# SIM800C_BoardSCH.net
KiCad netlist of a schematic drawn in Altium Designer
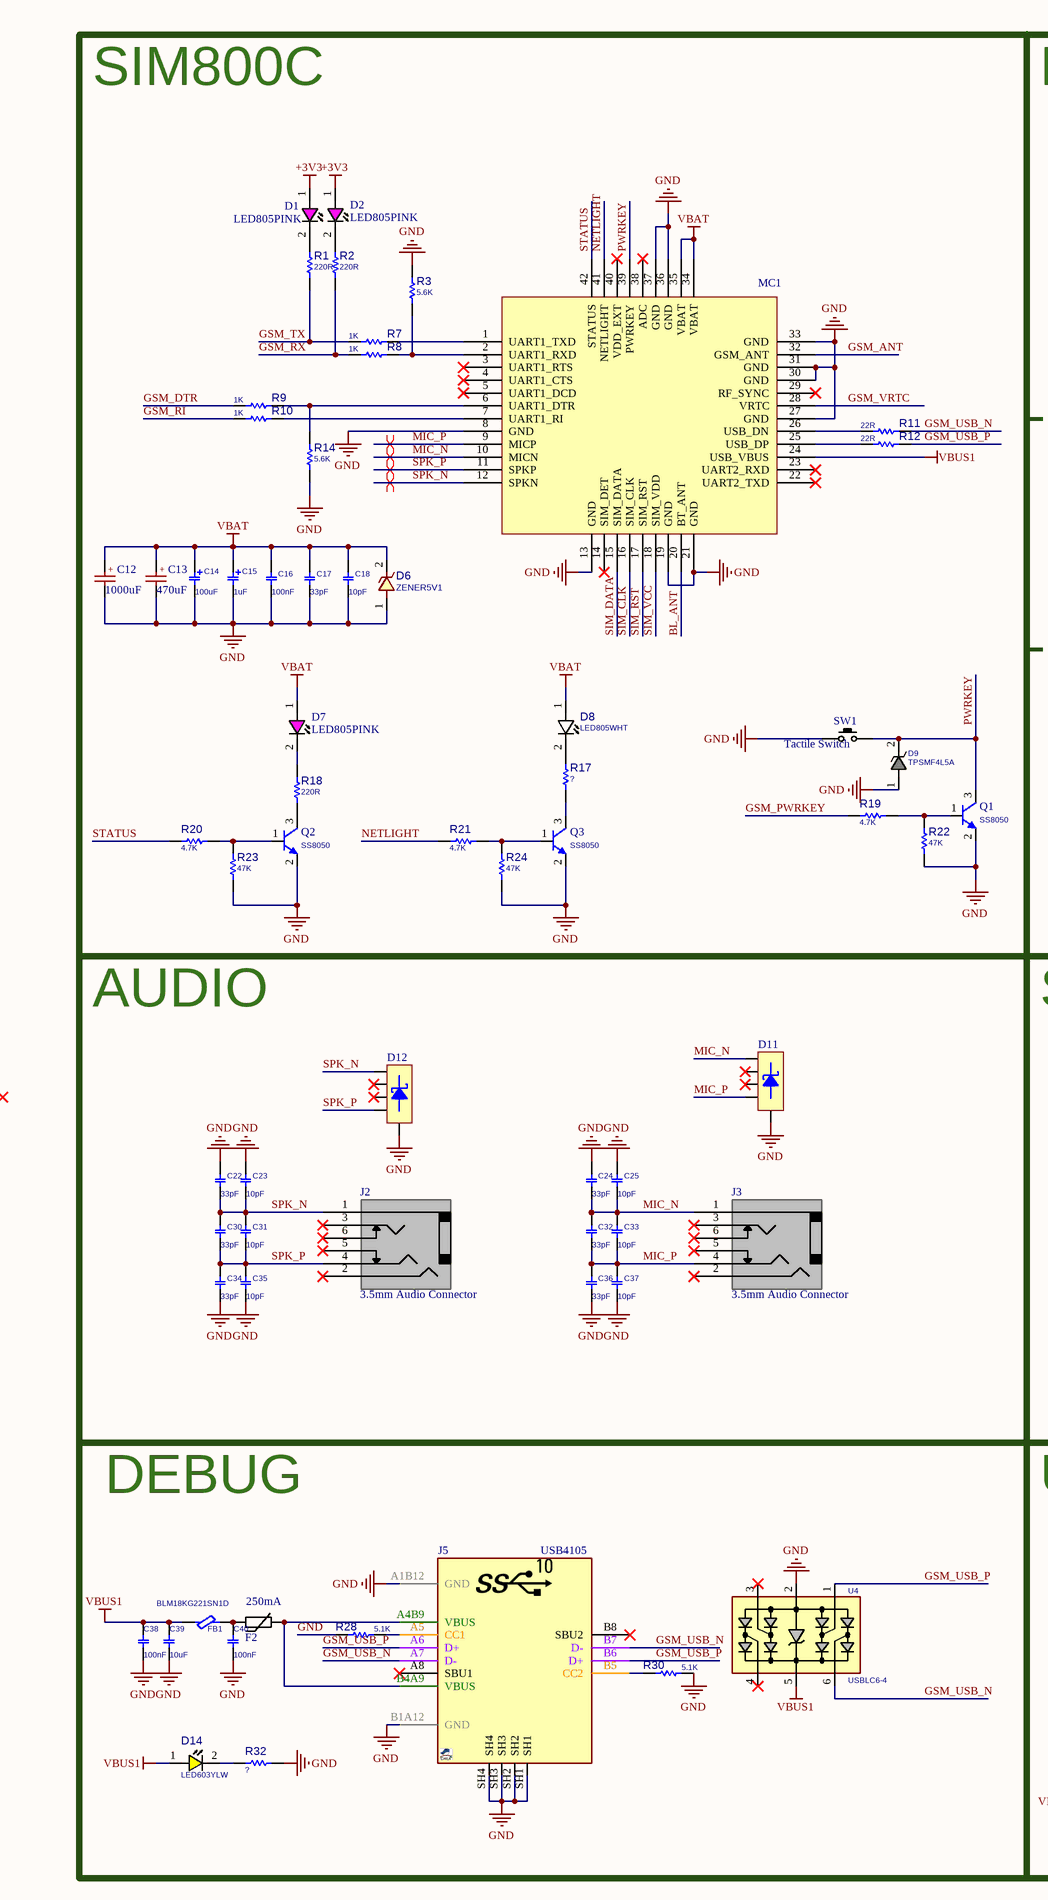
[diagram p0: SIM800C_BoardSCH.SchDoc, left]
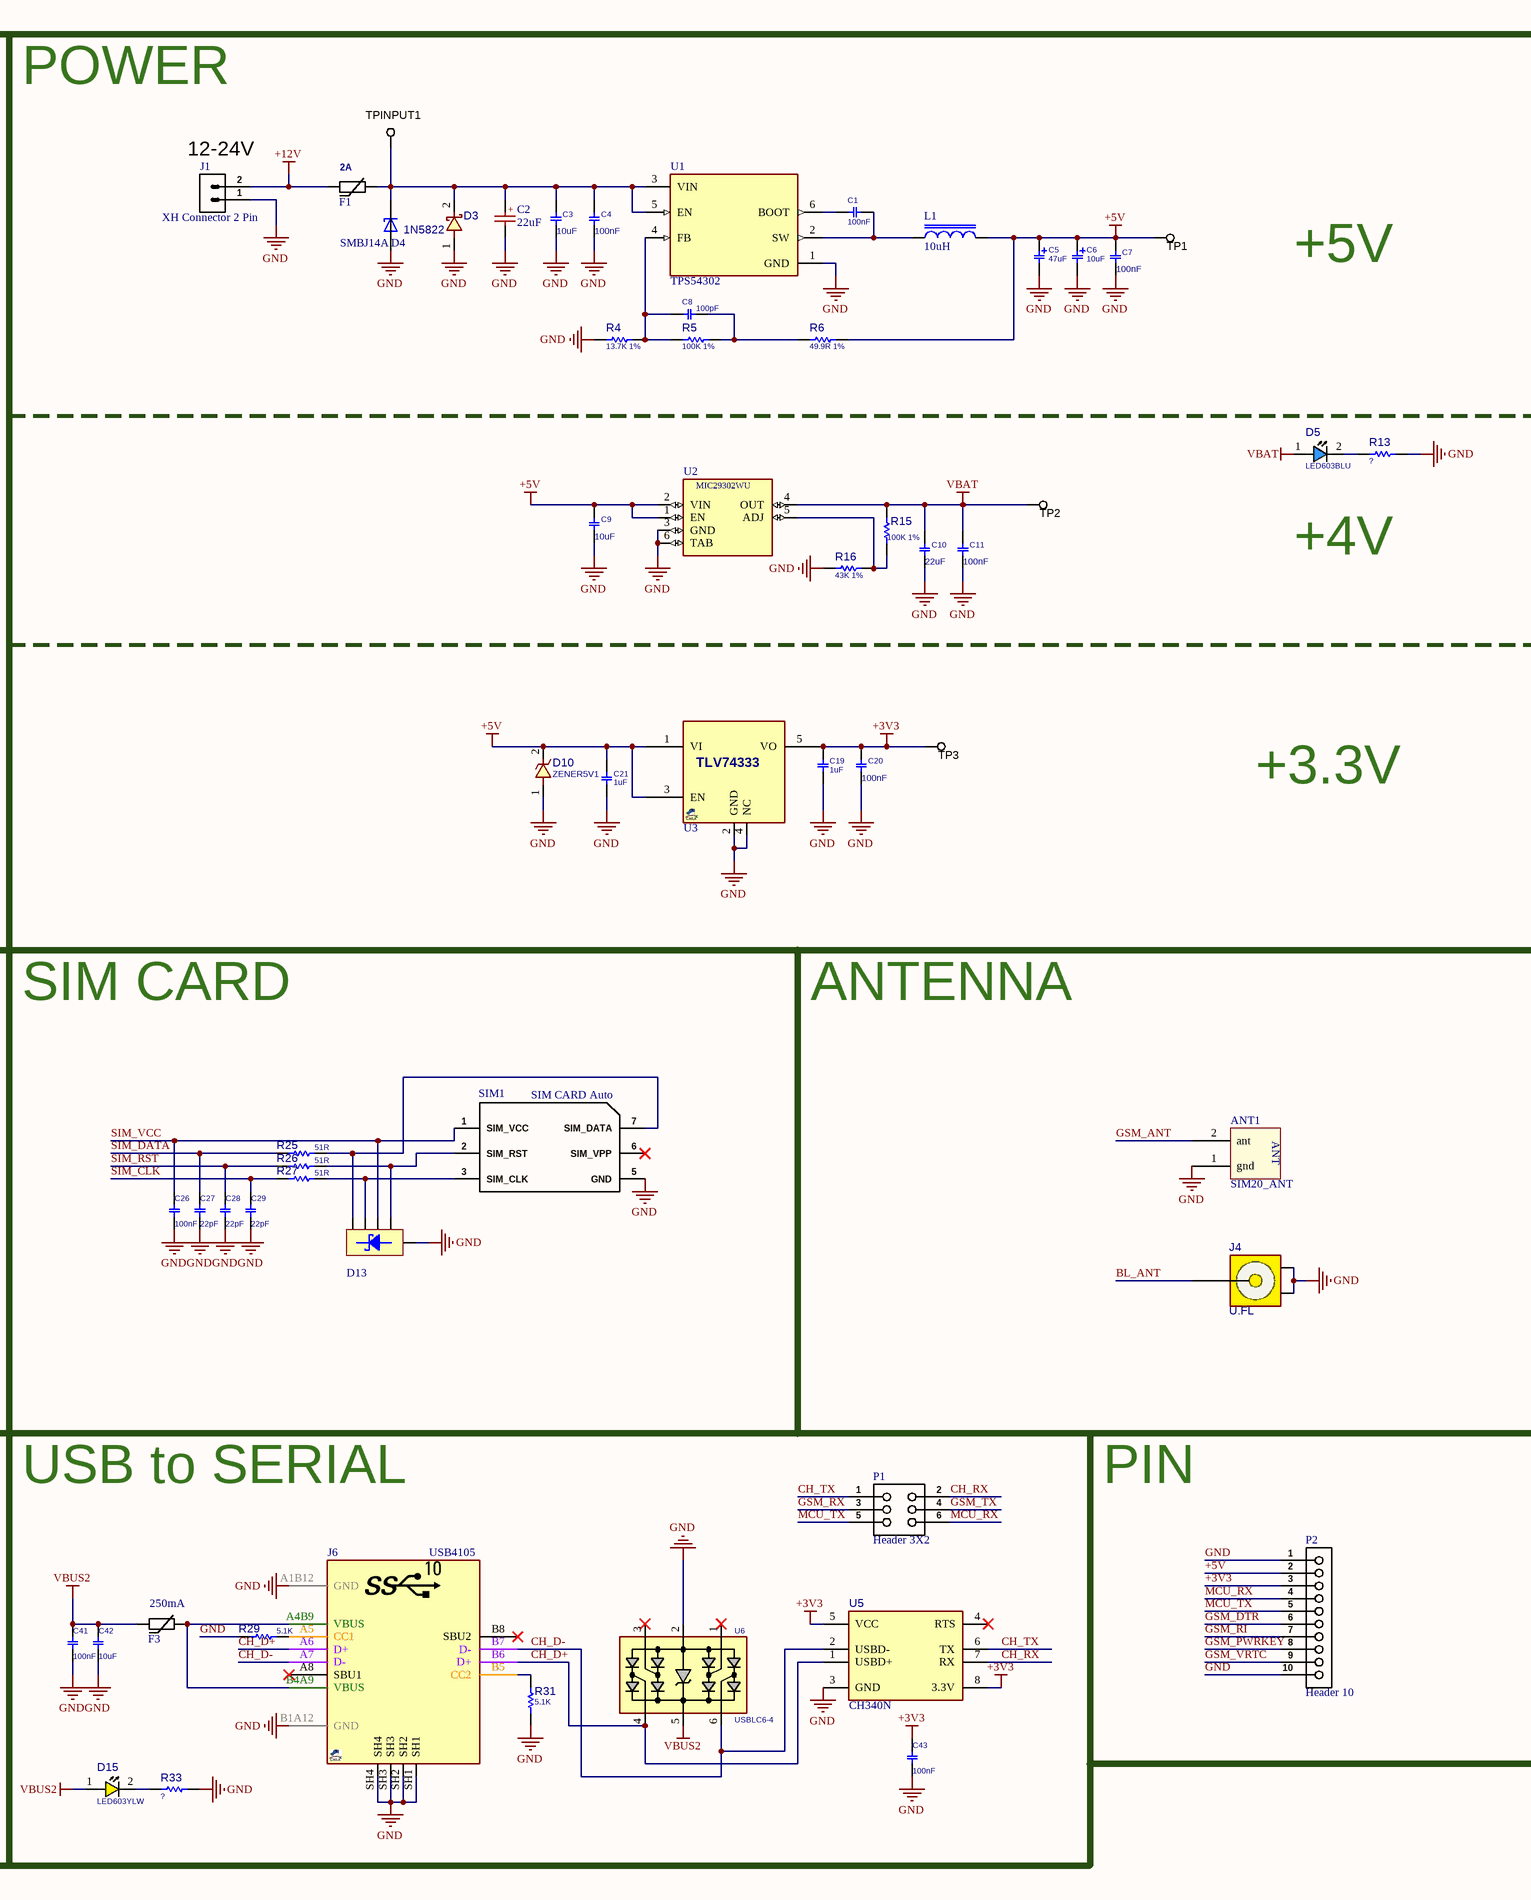
[diagram p1: SIM800C_BoardSCH.SchDoc, right]

(export (version "E")
  (design (tool "Eeschema 10.0.6"))
  (components
    (comp (ref "ANT1")
      (value "SIM20_ANT")
      (footprint "MY_SIM20_ANT")
      (description "ANT")
      (libsource (lib "AMINLIB") (part "SIM20_ANT"))
    )
    (comp (ref "C1")
      (value "100nF")
      (footprint "C0603")
      (description "CAP, MLCC, -F, -V, MATERIAL, -%, 0201")
      (fields (field (name "MANF_P#") "MANF_PART#"))
      (libsource (lib "passive_smd") (part "CAP_SMD_MLCC_0603"))
    )
    (comp (ref "C2")
      (value "22uF")
      (footprint "Cap SMD 6.3x5.4mm")
      (description "SMD Aluminum Electrolytic Capacitor")
      (fields
        (field (name "VOLTAGE") "12v")
        (field (name "TOLERANCE") "5%")
        (field (name "PUBLISHER") "Majid Derhambakhsh")
      )
      (libsource (lib "mBedLab Altium Library (2024-04-20)") (part "CAP Electrolytic SMD"))
    )
    (comp (ref "C3")
      (value "10uF")
      (footprint "C1206")
      (description "CAP, MLCC")
      (fields (field (name "MANF_P#") "MANF_PART#"))
      (libsource (lib "passive_smd") (part "CAP_SMD_MLCC_1206"))
    )
    (comp (ref "C4")
      (value "100nF")
      (footprint "C1206")
      (description "CAP, MLCC")
      (fields (field (name "MANF_P#") "MANF_PART#"))
      (libsource (lib "passive_smd") (part "CAP_SMD_MLCC_1206"))
    )
    (comp (ref "C5")
      (value "47uF")
      (footprint "C_TN_3216")
      (description "CAP, SMD, TAN,")
      (libsource (lib "passive_smd") (part "CAP_SMD_TAN"))
    )
    (comp (ref "C6")
      (value "10uF")
      (footprint "C_TN_3216")
      (description "CAP, SMD, TAN,")
      (libsource (lib "passive_smd") (part "CAP_SMD_TAN"))
    )
    (comp (ref "C7")
      (value "100nF")
      (footprint "C1206")
      (description "CAP, MLCC")
      (fields (field (name "MANF_P#") "MANF_PART#"))
      (libsource (lib "passive_smd") (part "CAP_SMD_MLCC_1206"))
    )
    (comp (ref "C8")
      (value "100pF")
      (footprint "C0603")
      (description "CAP, MLCC, -F, -V, MATERIAL, -%, 0201")
      (fields (field (name "MANF_P#") "MANF_PART#"))
      (libsource (lib "passive_smd") (part "CAP_SMD_MLCC_0603"))
    )
    (comp (ref "C9")
      (value "10uF")
      (footprint "C1206")
      (description "CAP, MLCC")
      (fields (field (name "MANF_P#") "MANF_PART#"))
      (libsource (lib "passive_smd") (part "CAP_SMD_MLCC_1206"))
    )
    (comp (ref "C10")
      (value "22uF")
      (footprint "C1206")
      (description "CAP, MLCC")
      (fields (field (name "MANF_P#") "MANF_PART#"))
      (libsource (lib "passive_smd") (part "CAP_SMD_MLCC_1206"))
    )
    (comp (ref "C11")
      (value "100nF")
      (footprint "C1206")
      (description "CAP, MLCC")
      (fields (field (name "MANF_P#") "MANF_PART#"))
      (libsource (lib "passive_smd") (part "CAP_SMD_MLCC_1206"))
    )
    (comp (ref "C12")
      (value "1000uF")
      (footprint "Cap SMD 8x10mm")
      (description "SMD Aluminum Electrolytic Capacitor")
      (fields
        (field (name "VOLTAGE") "12v")
        (field (name "TOLERANCE") "5%")
        (field (name "PUBLISHER") "Majid Derhambakhsh")
      )
      (libsource (lib "mBedLab Altium Library (2024-04-20)") (part "CAP Electrolytic SMD"))
    )
    (comp (ref "C13")
      (value "470uF")
      (footprint "Cap SMD 6.3x7.7mm")
      (description "SMD Aluminum Electrolytic Capacitor")
      (fields
        (field (name "VOLTAGE") "12v")
        (field (name "TOLERANCE") "5%")
        (field (name "PUBLISHER") "Majid Derhambakhsh")
      )
      (libsource (lib "mBedLab Altium Library (2024-04-20)") (part "CAP Electrolytic SMD"))
    )
    (comp (ref "C14")
      (value "100uF")
      (footprint "C_TN_3528_BLK")
      (description "CAP, SMD, TAN")
      (fields (field (name "MANF") "VISHAY") (field (name "MANF_P#") "T55A106M6R3C0300"))
      (libsource (lib "AVR_RCS") (part "CAP_SMD_TAN_4"))
    )
    (comp (ref "C15")
      (value "1uF")
      (footprint "C_TN_3216")
      (description "CAP, SMD, TAN,")
      (libsource (lib "passive_smd") (part "CAP_SMD_TAN"))
    )
    (comp (ref "C16")
      (value "100nF")
      (footprint "C0603")
      (description "CAP, MLCC, -F, -V, MATERIAL, -%, 0201")
      (fields (field (name "MANF_P#") "MANF_PART#"))
      (libsource (lib "passive_smd") (part "CAP_SMD_MLCC_0603"))
    )
    (comp (ref "C17")
      (value "33pF")
      (footprint "C0603")
      (description "CAP, MLCC, -F, -V, MATERIAL, -%, 0201")
      (fields (field (name "MANF_P#") "MANF_PART#"))
      (libsource (lib "passive_smd") (part "CAP_SMD_MLCC_0603"))
    )
    (comp (ref "C18")
      (value "10pF")
      (footprint "C0603")
      (description "CAP, MLCC, -F, -V, MATERIAL, -%, 0201")
      (fields (field (name "MANF_P#") "MANF_PART#"))
      (libsource (lib "passive_smd") (part "CAP_SMD_MLCC_0603"))
    )
    (comp (ref "C19")
      (value "1uF")
      (footprint "C1206")
      (description "CAP, MLCC, -F, -V, MATERIAL, -%, 0201")
      (fields (field (name "MANF_P#") "MANF_PART#"))
      (libsource (lib "passive_smd") (part "CAP_SMD_MLCC_1206"))
    )
    (comp (ref "C20")
      (value "100nF")
      (footprint "C1206")
      (description "CAP, MLCC")
      (fields (field (name "MANF_P#") "MANF_PART#"))
      (libsource (lib "passive_smd") (part "CAP_SMD_MLCC_1206"))
    )
    (comp (ref "C21")
      (value "1uF")
      (footprint "C1206")
      (description "CAP, MLCC, -F, -V, MATERIAL, -%, 0201")
      (fields (field (name "MANF_P#") "MANF_PART#"))
      (libsource (lib "passive_smd") (part "CAP_SMD_MLCC_1206"))
    )
    (comp (ref "C22")
      (value "33pF")
      (footprint "C0603")
      (description "CAP, MLCC, -F, -V, MATERIAL, -%, 0201")
      (fields (field (name "MANF_P#") "MANF_PART#"))
      (libsource (lib "passive_smd") (part "CAP_SMD_MLCC_0603"))
    )
    (comp (ref "C23")
      (value "10pF")
      (footprint "C0603")
      (description "CAP, MLCC, -F, -V, MATERIAL, -%, 0201")
      (fields (field (name "MANF_P#") "MANF_PART#"))
      (libsource (lib "passive_smd") (part "CAP_SMD_MLCC_0603"))
    )
    (comp (ref "C24")
      (value "33pF")
      (footprint "C0603")
      (description "CAP, MLCC, -F, -V, MATERIAL, -%, 0201")
      (fields (field (name "MANF_P#") "MANF_PART#"))
      (libsource (lib "passive_smd") (part "CAP_SMD_MLCC_0603"))
    )
    (comp (ref "C25")
      (value "10pF")
      (footprint "C0603")
      (description "CAP, MLCC, -F, -V, MATERIAL, -%, 0201")
      (fields (field (name "MANF_P#") "MANF_PART#"))
      (libsource (lib "passive_smd") (part "CAP_SMD_MLCC_0603"))
    )
    (comp (ref "C26")
      (value "100nF")
      (footprint "C0603")
      (description "CAP, MLCC, -F, -V, MATERIAL, -%, 0201")
      (fields (field (name "MANF_P#") "MANF_PART#"))
      (libsource (lib "passive_smd") (part "CAP_SMD_MLCC_0603"))
    )
    (comp (ref "C27")
      (value "22pF")
      (footprint "C0603")
      (description "CAP, MLCC, -F, -V, MATERIAL, -%, 0201")
      (fields (field (name "MANF_P#") "MANF_PART#"))
      (libsource (lib "passive_smd") (part "CAP_SMD_MLCC_0603"))
    )
    (comp (ref "C28")
      (value "22pF")
      (footprint "C0603")
      (description "CAP, MLCC, -F, -V, MATERIAL, -%, 0201")
      (fields (field (name "MANF_P#") "MANF_PART#"))
      (libsource (lib "passive_smd") (part "CAP_SMD_MLCC_0603"))
    )
    (comp (ref "C29")
      (value "22pF")
      (footprint "C0603")
      (description "CAP, MLCC, -F, -V, MATERIAL, -%, 0201")
      (fields (field (name "MANF_P#") "MANF_PART#"))
      (libsource (lib "passive_smd") (part "CAP_SMD_MLCC_0603"))
    )
    (comp (ref "C30")
      (value "33pF")
      (footprint "C0603")
      (description "CAP, MLCC, -F, -V, MATERIAL, -%, 0201")
      (fields (field (name "MANF_P#") "MANF_PART#"))
      (libsource (lib "passive_smd") (part "CAP_SMD_MLCC_0603"))
    )
    (comp (ref "C31")
      (value "10pF")
      (footprint "C0603")
      (description "CAP, MLCC, -F, -V, MATERIAL, -%, 0201")
      (fields (field (name "MANF_P#") "MANF_PART#"))
      (libsource (lib "passive_smd") (part "CAP_SMD_MLCC_0603"))
    )
    (comp (ref "C32")
      (value "33pF")
      (footprint "C0603")
      (description "CAP, MLCC, -F, -V, MATERIAL, -%, 0201")
      (fields (field (name "MANF_P#") "MANF_PART#"))
      (libsource (lib "passive_smd") (part "CAP_SMD_MLCC_0603"))
    )
    (comp (ref "C33")
      (value "10pF")
      (footprint "C0603")
      (description "CAP, MLCC, -F, -V, MATERIAL, -%, 0201")
      (fields (field (name "MANF_P#") "MANF_PART#"))
      (libsource (lib "passive_smd") (part "CAP_SMD_MLCC_0603"))
    )
    (comp (ref "C34")
      (value "33pF")
      (footprint "C0603")
      (description "CAP, MLCC, -F, -V, MATERIAL, -%, 0201")
      (fields (field (name "MANF_P#") "MANF_PART#"))
      (libsource (lib "passive_smd") (part "CAP_SMD_MLCC_0603"))
    )
    (comp (ref "C35")
      (value "10pF")
      (footprint "C0603")
      (description "CAP, MLCC, -F, -V, MATERIAL, -%, 0201")
      (fields (field (name "MANF_P#") "MANF_PART#"))
      (libsource (lib "passive_smd") (part "CAP_SMD_MLCC_0603"))
    )
    (comp (ref "C36")
      (value "33pF")
      (footprint "C0603")
      (description "CAP, MLCC, -F, -V, MATERIAL, -%, 0201")
      (fields (field (name "MANF_P#") "MANF_PART#"))
      (libsource (lib "passive_smd") (part "CAP_SMD_MLCC_0603"))
    )
    (comp (ref "C37")
      (value "10pF")
      (footprint "C0603")
      (description "CAP, MLCC, -F, -V, MATERIAL, -%, 0201")
      (fields (field (name "MANF_P#") "MANF_PART#"))
      (libsource (lib "passive_smd") (part "CAP_SMD_MLCC_0603"))
    )
    (comp (ref "C38")
      (value "100nF")
      (footprint "C0603")
      (description "CAP, MLCC, -F, -V, MATERIAL, -%, 0201")
      (fields (field (name "MANF_P#") "MANF_PART#"))
      (libsource (lib "passive_smd") (part "CAP_SMD_MLCC_0603"))
    )
    (comp (ref "C39")
      (value "10uF")
      (footprint "C0603")
      (description "CAP, MLCC, -F, -V, MATERIAL, -%, 0201")
      (fields (field (name "MANF_P#") "MANF_PART#"))
      (libsource (lib "passive_smd") (part "CAP_SMD_MLCC_0603"))
    )
    (comp (ref "C40")
      (value "100nF")
      (footprint "C0603")
      (description "CAP, MLCC, -F, -V, MATERIAL, -%, 0201")
      (fields (field (name "MANF_P#") "MANF_PART#"))
      (libsource (lib "passive_smd") (part "CAP_SMD_MLCC_0603"))
    )
    (comp (ref "C41")
      (value "100nF")
      (footprint "C0603")
      (description "CAP, MLCC, -F, -V, MATERIAL, -%, 0201")
      (fields (field (name "MANF_P#") "MANF_PART#"))
      (libsource (lib "passive_smd") (part "CAP_SMD_MLCC_0603"))
    )
    (comp (ref "C42")
      (value "10uF")
      (footprint "C0603")
      (description "CAP, MLCC, -F, -V, MATERIAL, -%, 0201")
      (fields (field (name "MANF_P#") "MANF_PART#"))
      (libsource (lib "passive_smd") (part "CAP_SMD_MLCC_0603"))
    )
    (comp (ref "C43")
      (value "100nF")
      (footprint "C0603")
      (description "CAP, MLCC, -F, -V, MATERIAL, -%, 0201")
      (fields (field (name "MANF_P#") "MANF_PART#"))
      (libsource (lib "passive_smd") (part "CAP_SMD_MLCC_0603"))
    )
    (comp (ref "D1")
      (value "LED805PINK")
      (footprint "LED_Pink_0805")
      (description "LED, SMD, 0805, PINK")
      (libsource (lib "Mehrdad") (part "LED_Pink"))
    )
    (comp (ref "D2")
      (value "LED805PINK")
      (footprint "LED_Pink_0805")
      (description "LED, SMD, 0805, PINK")
      (libsource (lib "Mehrdad") (part "LED_Pink"))
    )
    (comp (ref "D3")
      (value "1N5822")
      (footprint "D_SMA")
      (description "DIODE, SCHOTTKY, 40V, 3A")
      (fields (field (name "MANF") "DIODES"))
      (libsource (lib "diode") (part "DIODE_SMD_SCHOTTKY_1N5822"))
    )
    (comp (ref "D4")
      (value "SMBJ14A")
      (footprint "SMBJ14A")
      (description "TVS Diode Uni-directional 14V SMB")
      (libsource (lib "Mehrdad") (part "SMBJ14A"))
    )
    (comp (ref "D5")
      (value "LED603BLU")
      (footprint "LED0603BLU")
      (description "LED, SMD, 0603, BLUE")
      (fields (field (name "MANF") "MANF") (field (name "MANF_P#") "MANF_PART#"))
      (libsource (lib "led(diode)") (part "LED_SMD_0603_BLU"))
    )
    (comp (ref "D6")
      (value "ZENER5V1")
      (footprint "D_SOD123W")
      (description "DIODE, ZENER, 1W, 5.1V")
      (fields (field (name "MANF") "Diodes") (field (name "MANF_P#") "BZT52HC5V1WF-7"))
      (libsource (lib "AVR_RCS") (part "DIODE_SMD_ZENER_BZT52HC5V1"))
    )
    (comp (ref "D7")
      (value "LED805PINK")
      (footprint "LED_Pink_0805")
      (description "LED, SMD, 0805, PINK")
      (libsource (lib "Mehrdad") (part "LED_Pink"))
    )
    (comp (ref "D8")
      (value "LED805WHT")
      (footprint "LED0805WHT")
      (description "LED, SMD, 0805, WHITE")
      (fields (field (name "MANF") "MANF") (field (name "MANF_P#") "MANF_PART#"))
      (libsource (lib "led(diode)") (part "LED_SMD_0805_WHT"))
    )
    (comp (ref "D9")
      (value "TPSMF4L5A")
      (footprint "D_SOD123W")
      (description "TVS, ESD PROTECT")
      (fields (field (name "MANF_P#") "TPSMF4L33A") (field (name "MANF") "Littelfuse"))
      (libsource (lib "protect_tvs_esd_fuse") (part "TVS_TPSMF4L33A"))
    )
    (comp (ref "D10")
      (value "ZENER5V1")
      (footprint "D_SOD123W")
      (description "DIODE, ZENER, 1W, 5.1V")
      (fields (field (name "MANF") "Diodes") (field (name "MANF_P#") "BZT52HC5V1WF-7"))
      (libsource (lib "AVR_RCS") (part "DIODE_SMD_ZENER_BZT52HC5V1"))
    )
    (comp (ref "D11")
      (value "SMF-05")
      (footprint "SC70-5_N")
      (description "TVS Diode Array")
      (fields (field (name "VALIDATION") "Valid"))
      (libsource (lib "aKaReZa") (part "Semi_Diod_TVS_SMF05"))
    )
    (comp (ref "D12")
      (value "SMF-05")
      (footprint "SC70-5_N")
      (description "TVS Diode Array")
      (fields (field (name "VALIDATION") "Valid"))
      (libsource (lib "aKaReZa") (part "Semi_Diod_TVS_SMF05"))
    )
    (comp (ref "D13")
      (value "SMF-05")
      (footprint "SC70-5_N")
      (description "TVS Diode Array")
      (fields (field (name "VALIDATION") "Valid"))
      (libsource (lib "") (part "Semi_Diod_TVS_SMF05_1"))
    )
    (comp (ref "D14")
      (value "LED603YLW")
      (footprint "LED0603YLW")
      (description "LED, SMD, 0603, YELLOW")
      (fields (field (name "MANF") "MANF") (field (name "MANF_P#") "MANF_PART#"))
      (libsource (lib "led(diode)") (part "LED_SMD_0603_YLW"))
    )
    (comp (ref "D15")
      (value "LED603YLW")
      (footprint "LED0603YLW")
      (description "LED, SMD, 0603, YELLOW")
      (fields (field (name "MANF") "MANF") (field (name "MANF_P#") "MANF_PART#"))
      (libsource (lib "led(diode)") (part "LED_SMD_0603_YLW"))
    )
    (comp (ref "F1")
      (value "2A")
      (footprint "FUSE1206 (3216)")
      (fields (field (name "PUBLISHER") "Majid Derhambakhsh"))
      (libsource (lib "mBedLab Altium Library (2024-04-20)") (part "PPTC Resettable Fuses"))
    )
    (comp (ref "F2")
      (value "250mA")
      (footprint "FUSE0603 (1608)")
      (fields (field (name "PUBLISHER") "Majid Derhambakhsh"))
      (libsource (lib "mBedLab Altium Library (2024-04-20)") (part "PPTC Resettable Fuses"))
    )
    (comp (ref "F3")
      (value "250mA")
      (footprint "FUSE0603 (1608)")
      (fields (field (name "PUBLISHER") "Majid Derhambakhsh"))
      (libsource (lib "mBedLab Altium Library (2024-04-20)") (part "PPTC Resettable Fuses"))
    )
    (comp (ref "FB1")
      (value "BLM18KG221SN1D")
      (footprint "L0603")
      (description "FERRITE_Bead, 0603, 2A, 50mOhm, 120@100MHz")
      (fields (field (name "MANF") "MURATA") (field (name "MANF_P#") "BLM18PG121SN1D"))
      (libsource (lib "emi_filter") (part "FBEAD_SMD_BLM18PG121"))
    )
    (comp (ref "J1")
      (value "XH Connector 2 Pin")
      (footprint "XH 2 Pin Right (CWF) - 2.5mm")
      (description "XH, 2-Pin")
      (fields (field (name "PUBLISHER") "Majid Derhambakhsh"))
      (libsource (lib "mBedLab Altium Library (2024-04-20)") (part "XH 2"))
    )
    (comp (ref "J2")
      (value "3.5mm Audio Connector")
      (footprint "PJ311D")
      (libsource (lib "Mehrdad") (part "PJ311D"))
    )
    (comp (ref "J3")
      (value "3.5mm Audio Connector")
      (footprint "PJ311D")
      (libsource (lib "Mehrdad") (part "PJ311D"))
    )
    (comp (ref "J4")
      (value "U.FL")
      (footprint "UFL")
      (description "CONN, RF, U.FL, STRAIGHT, Ultra Miniature Coaxial")
      (fields
        (field (name "MANF_P#") "CONUFL001-SMD, U.FL-R-SMT-1(10), 128-0711-201")
        (field (name "MANF") "Linx, Hirose, Cinch")
      )
      (libsource (lib "conn_rf") (part "CONN_RF_UFL"))
    )
    (comp (ref "J5")
      (value "USB4105")
      (footprint "USBC_SMD_16_USB4105")
      (description "CONN, USB, Type C, USB 2.0, Right-Angle, SMD")
      (fields (field (name "MANF") "GCT") (field (name "MANF_P#") "USB4105-GF-A"))
      (libsource (lib "conn_usbc") (part "CONN_USBC_SMD_16_USB4105"))
    )
    (comp (ref "J6")
      (value "USB4105")
      (footprint "USBC_SMD_16_USB4105")
      (description "CONN, USB, Type C, USB 2.0, Right-Angle, SMD")
      (fields (field (name "MANF") "GCT") (field (name "MANF_P#") "USB4105-GF-A"))
      (libsource (lib "conn_usbc") (part "CONN_USBC_SMD_16_USB4105"))
    )
    (comp (ref "L1")
      (value "10uH")
      (footprint "SMD Inductor 1")
      (description "1210 (3225)  Part number : DFE322512F-100M=P2")
      (libsource (lib "Mehrdad") (part "SMD Inductor 1"))
    )
    (comp (ref "MC1")
      (value "Sim800C")
      (footprint "SIM800C")
      (description "SimCom GSM/GPRS Module")
      (fields (field (name "VALIDATION") "NT"))
      (libsource (lib "aKaReZa") (part "ModSen_Com_Sim800C"))
    )
    (comp (ref "P1")
      (value "Header 3X2")
      (footprint "HDR 2X3 Male Top")
      (description "Header, 3-Pin, Dual row")
      (fields (field (name "PUBLISHER") "Majid Derhambakhsh"))
      (libsource (lib "mBedLab Altium Library (2024-04-20)") (part "Header 3X2"))
    )
    (comp (ref "P2")
      (value "Header 10")
      (footprint "HDR 1X10 Male Top")
      (description "Header, 10-Pin")
      (fields (field (name "PUBLISHER") "Majid Derhambakhsh"))
      (libsource (lib "mBedLab Altium Library (2024-04-20)") (part "Header 10"))
    )
    (comp (ref "Q1")
      (value "SS8050")
      (footprint "SOT23_3")
      (description "BJT, NPN, 25v, 1.5A, SMD, SOT23")
      (fields (field (name "MANF") "GALAXY"))
      (libsource (lib "transistor_bjt") (part "NPN_SS8050_SOT23"))
    )
    (comp (ref "Q2")
      (value "SS8050")
      (footprint "SOT23_3")
      (description "BJT, NPN, 25v, 1.5A, SMD, SOT23")
      (fields (field (name "MANF") "GALAXY"))
      (libsource (lib "transistor_bjt") (part "NPN_SS8050_SOT23"))
    )
    (comp (ref "Q3")
      (value "SS8050")
      (footprint "SOT23_3")
      (description "BJT, NPN, 25v, 1.5A, SMD, SOT23")
      (fields (field (name "MANF") "GALAXY"))
      (libsource (lib "transistor_bjt") (part "NPN_SS8050_SOT23"))
    )
    (comp (ref "R1")
      (value "220R")
      (footprint "R0603")
      (description "RESISTOR, SMD")
      (libsource (lib "passive_smd") (part "RES_SMD_0603"))
    )
    (comp (ref "R2")
      (value "220R")
      (footprint "R0603")
      (description "RESISTOR, SMD")
      (libsource (lib "passive_smd") (part "RES_SMD_0603"))
    )
    (comp (ref "R3")
      (value "5.6K")
      (footprint "R0603")
      (description "RESISTOR, SMD")
      (libsource (lib "passive_smd") (part "RES_SMD_0603"))
    )
    (comp (ref "R4")
      (value "13.7K 1%")
      (footprint "R0603")
      (description "RESISTOR, SMD")
      (libsource (lib "passive_smd") (part "RES_SMD_0603"))
    )
    (comp (ref "R5")
      (value "100K 1%")
      (footprint "R0603")
      (description "RESISTOR, SMD")
      (libsource (lib "passive_smd") (part "RES_SMD_0603"))
    )
    (comp (ref "R6")
      (value "49.9R 1%")
      (footprint "R0603")
      (description "RESISTOR, SMD")
      (libsource (lib "passive_smd") (part "RES_SMD_0603"))
    )
    (comp (ref "R7")
      (value "1K")
      (footprint "R0603")
      (description "RESISTOR, SMD")
      (libsource (lib "passive_smd") (part "RES_SMD_0603"))
    )
    (comp (ref "R8")
      (value "1K")
      (footprint "R0603")
      (description "RESISTOR, SMD")
      (libsource (lib "passive_smd") (part "RES_SMD_0603"))
    )
    (comp (ref "R9")
      (value "1K")
      (footprint "R0603")
      (description "RESISTOR, SMD")
      (libsource (lib "passive_smd") (part "RES_SMD_0603"))
    )
    (comp (ref "R10")
      (value "1K")
      (footprint "R0603")
      (description "RESISTOR, SMD")
      (libsource (lib "passive_smd") (part "RES_SMD_0603"))
    )
    (comp (ref "R11")
      (value "22R")
      (footprint "R0603")
      (description "RESISTOR, SMD")
      (libsource (lib "passive_smd") (part "RES_SMD_0603"))
    )
    (comp (ref "R12")
      (value "22R")
      (footprint "R0603")
      (description "RESISTOR, SMD")
      (libsource (lib "passive_smd") (part "RES_SMD_0603"))
    )
    (comp (ref "R13")
      (value "?")
      (footprint "R0603")
      (description "RESISTOR, SMD")
      (libsource (lib "passive_smd") (part "RES_SMD_0603"))
    )
    (comp (ref "R14")
      (value "5.6K")
      (footprint "R0603")
      (description "RESISTOR, SMD")
      (libsource (lib "passive_smd") (part "RES_SMD_0603"))
    )
    (comp (ref "R15")
      (value "100K 1%")
      (footprint "R0603")
      (description "RESISTOR, SMD")
      (libsource (lib "passive_smd") (part "RES_SMD_0603"))
    )
    (comp (ref "R16")
      (value "43K 1%")
      (footprint "R0603")
      (description "RESISTOR, SMD")
      (libsource (lib "passive_smd") (part "RES_SMD_0603"))
    )
    (comp (ref "R17")
      (value "?")
      (footprint "R0603")
      (description "RESISTOR, SMD")
      (libsource (lib "passive_smd") (part "RES_SMD_0603"))
    )
    (comp (ref "R18")
      (value "220R")
      (footprint "R0603")
      (description "RESISTOR, SMD")
      (libsource (lib "passive_smd") (part "RES_SMD_0603"))
    )
    (comp (ref "R19")
      (value "4.7K")
      (footprint "R0603")
      (description "RESISTOR, SMD")
      (libsource (lib "passive_smd") (part "RES_SMD_0603"))
    )
    (comp (ref "R20")
      (value "4.7K")
      (footprint "R0603")
      (description "RESISTOR, SMD")
      (libsource (lib "passive_smd") (part "RES_SMD_0603"))
    )
    (comp (ref "R21")
      (value "4.7K")
      (footprint "R0603")
      (description "RESISTOR, SMD")
      (libsource (lib "passive_smd") (part "RES_SMD_0603"))
    )
    (comp (ref "R22")
      (value "47K")
      (footprint "R0603")
      (description "RESISTOR, SMD")
      (libsource (lib "passive_smd") (part "RES_SMD_0603"))
    )
    (comp (ref "R23")
      (value "47K")
      (footprint "R0603")
      (description "RESISTOR, SMD")
      (libsource (lib "passive_smd") (part "RES_SMD_0603"))
    )
    (comp (ref "R24")
      (value "47K")
      (footprint "R0603")
      (description "RESISTOR, SMD")
      (libsource (lib "passive_smd") (part "RES_SMD_0603"))
    )
    (comp (ref "R25")
      (value "51R")
      (footprint "R0603")
      (description "RESISTOR, SMD")
      (libsource (lib "passive_smd") (part "RES_SMD_0603"))
    )
    (comp (ref "R26")
      (value "51R")
      (footprint "R0603")
      (description "RESISTOR, SMD")
      (libsource (lib "passive_smd") (part "RES_SMD_0603"))
    )
    (comp (ref "R27")
      (value "51R")
      (footprint "R0603")
      (description "RESISTOR, SMD")
      (libsource (lib "passive_smd") (part "RES_SMD_0603"))
    )
    (comp (ref "R28")
      (value "5.1K")
      (footprint "R0603")
      (description "RESISTOR, SMD")
      (libsource (lib "passive_smd") (part "RES_SMD_0603"))
    )
    (comp (ref "R29")
      (value "5.1K")
      (footprint "R0603")
      (description "RESISTOR, SMD")
      (libsource (lib "passive_smd") (part "RES_SMD_0603"))
    )
    (comp (ref "R30")
      (value "5.1K")
      (footprint "R0603")
      (description "RESISTOR, SMD")
      (libsource (lib "passive_smd") (part "RES_SMD_0603"))
    )
    (comp (ref "R31")
      (value "5.1K")
      (footprint "R0603")
      (description "RESISTOR, SMD")
      (libsource (lib "passive_smd") (part "RES_SMD_0603"))
    )
    (comp (ref "R32")
      (value "?")
      (footprint "R0603")
      (description "RESISTOR, SMD")
      (libsource (lib "passive_smd") (part "RES_SMD_0603"))
    )
    (comp (ref "R33")
      (value "?")
      (footprint "R0603")
      (description "RESISTOR, SMD")
      (libsource (lib "passive_smd") (part "RES_SMD_0603"))
    )
    (comp (ref "SIM1")
      (value "SIM CARD Auto")
      (footprint "SIM CARD MICRO 6 PIN AUTO 1")
      (description "SIM CARD 6 Pin Auto")
      (fields (field (name "PUBLISHER") "Majid Derhambakhsh"))
      (libsource (lib "mBedLab Altium Library (2024-04-20)") (part "SIM CARD micro auto"))
    )
    (comp (ref "SW1")
      (value "Tactile Switch")
      (footprint "Tactile Switch")
      (description "3x6x5 mm - 2 Pin")
      (libsource (lib "Mehrdad") (part "Tactile Switch"))
    )
    (comp (ref "TP1")
      (value "TESTPOINT_SMD")
      (footprint "TPSMD_S1")
      (description "TEST POINT")
      (fields (field (name "MANF") "MANF") (field (name "MANF_P#") "MANF_P#"))
      (libsource (lib "test-tp_jumper") (part "TESTPOINT_SMD"))
    )
    (comp (ref "TP2")
      (value "TESTPOINT_SMD")
      (footprint "TPSMD_S1")
      (description "TEST POINT")
      (fields (field (name "MANF") "MANF") (field (name "MANF_P#") "MANF_P#"))
      (libsource (lib "test-tp_jumper") (part "TESTPOINT_SMD"))
    )
    (comp (ref "TP3")
      (value "TESTPOINT_SMD")
      (footprint "TPSMD_S1")
      (description "TEST POINT")
      (fields (field (name "MANF") "MANF") (field (name "MANF_P#") "MANF_P#"))
      (libsource (lib "test-tp_jumper") (part "TESTPOINT_SMD"))
    )
    (comp (ref "TPINPUT1")
      (value "TESTPOINT_SMD")
      (footprint "TPSMD_S1")
      (description "TEST POINT")
      (fields (field (name "MANF") "MANF") (field (name "MANF_P#") "MANF_P#"))
      (libsource (lib "test-tp_jumper") (part "TESTPOINT_SMD"))
    )
    (comp (ref "U1")
      (value "TPS54302")
      (footprint "TPS54302")
      (description "4.5-V to 28-V Input, 3-A Output, EMI Friendly\r\nSynchronous Step-Down Converter")
      (libsource (lib "Mehrdad") (part "TPS54302"))
    )
    (comp (ref "U2")
      (value "MIC29302")
      (footprint "MIC29302")
      (description "Linear Voltage Regulator IC 1 Output 3A TO-263-5")
      (libsource (lib "Mehrdad") (part "MIC29302"))
    )
    (comp (ref "U3")
      (value "TLV74333")
      (footprint "SOT23_5")
      (description "REG, Linear, LDO0.12V, Fixed, 300mA, VIN1.4~5.5V, VOUT1~5.5V, SOT-23-5")
      (fields (field (name "MANF") "Texas Instruments") (field (name "MANF_P#") "TLV74333PDQN"))
      (libsource (lib "pwr_reg_linear_LDO_highPSRR") (part "VREG_TLV74333_SOT23"))
    )
    (comp (ref "U4")
      (value "USBLC6-4")
      (footprint "SOT23_6")
      (description "TVS, ESD PROTECT, 4CH")
      (fields (field (name "MANF_P#") "USBLC6-4SC6") (field (name "MANF") "ST"))
      (libsource (lib "protect_tvs_esd_fuse") (part "TVS_X4_USBLC6-4SC6"))
    )
    (comp (ref "U5")
      (value "CH340N")
      (footprint "SO8_narrow_N")
      (description "TTL To USB Chip")
      (fields (field (name "VALIDATION") "Valid"))
      (libsource (lib "aKaReZa") (part "IC_Converter_CH340N"))
    )
    (comp (ref "U6")
      (value "USBLC6-4")
      (footprint "SOT23_6")
      (description "TVS, ESD PROTECT, 4CH")
      (fields (field (name "MANF_P#") "USBLC6-4SC6") (field (name "MANF") "ST"))
      (libsource (lib "protect_tvs_esd_fuse") (part "TVS_X4_USBLC6-4SC6"))
    )
  )
  (nets
    (net (code "1") (name "+3V3") (class "Default")
      (node (ref "C19") (pin "1") (pinfunction "1_1") (pintype "passive"))
      (node (ref "C20") (pin "2") (pinfunction "2_2") (pintype "passive"))
      (node (ref "C43") (pin "2") (pinfunction "2_2") (pintype "passive"))
      (node (ref "D1") (pin "1") (pinfunction "ANODE_1") (pintype "passive"))
      (node (ref "D2") (pin "1") (pinfunction "ANODE_1") (pintype "passive"))
      (node (ref "P2") (pin "3") (pinfunction "3_3") (pintype "passive"))
      (node (ref "TP3") (pin "1") (pinfunction "1_1") (pintype "passive"))
      (node (ref "U3") (pin "5") (pinfunction "VO_5") (pintype "passive"))
      (node (ref "U5") (pin "5") (pinfunction "VCC_5") (pintype "passive"))
      (node (ref "U5") (pin "8") (pinfunction "3.3V_8") (pintype "passive"))
    )
    (net (code "2") (name "+5V") (class "Default")
      (node (ref "C21") (pin "1") (pinfunction "1_1") (pintype "passive"))
      (node (ref "C5") (pin "1") (pinfunction "1_1") (pintype "passive"))
      (node (ref "C6") (pin "1") (pinfunction "1_1") (pintype "passive"))
      (node (ref "C7") (pin "2") (pinfunction "2_2") (pintype "passive"))
      (node (ref "C9") (pin "2") (pinfunction "2_2") (pintype "passive"))
      (node (ref "D10") (pin "2") (pinfunction "2_2") (pintype "passive"))
      (node (ref "L1") (pin "2") (pinfunction "2_2") (pintype "passive"))
      (node (ref "P2") (pin "2") (pinfunction "2_2") (pintype "passive"))
      (node (ref "R6") (pin "2") (pinfunction "2_2") (pintype "passive"))
      (node (ref "TP1") (pin "1") (pinfunction "1_1") (pintype "passive"))
      (node (ref "U2") (pin "1") (pinfunction "EN_1") (pintype "bidirectional"))
      (node (ref "U2") (pin "2") (pinfunction "VIN_2") (pintype "bidirectional"))
      (node (ref "U3") (pin "1") (pinfunction "VI_1") (pintype "passive"))
      (node (ref "U3") (pin "3") (pinfunction "EN_3") (pintype "passive"))
    )
    (net (code "3") (name "+12V") (class "Default")
      (node (ref "F1") (pin "1") (pinfunction "1_1") (pintype "passive"))
      (node (ref "J1") (pin "2") (pinfunction "2_2") (pintype "passive"))
    )
    (net (code "4") (name "/BL_ANT") (class "Default")
      (node (ref "J4") (pin "1") (pinfunction "SIG_1") (pintype "passive"))
      (node (ref "MC1") (pin "20") (pinfunction "BT_ANT_20") (pintype "passive"))
    )
    (net (code "5") (name "/CH_D+") (class "Default")
      (node (ref "J6") (pin "A6") (pinfunction "D+_A6") (pintype "passive"))
      (node (ref "J6") (pin "B6") (pinfunction "D+_B6") (pintype "passive"))
      (node (ref "U5") (pin "1") (pinfunction "USBD+_1") (pintype "passive"))
      (node (ref "U6") (pin "4") (pinfunction "4_4") (pintype "passive"))
    )
    (net (code "6") (name "/CH_D-") (class "Default")
      (node (ref "J6") (pin "A7") (pinfunction "D-_A7") (pintype "passive"))
      (node (ref "J6") (pin "B7") (pinfunction "D-_B7") (pintype "passive"))
      (node (ref "U5") (pin "2") (pinfunction "USBD-_2") (pintype "passive"))
      (node (ref "U6") (pin "6") (pinfunction "6_6") (pintype "passive"))
    )
    (net (code "7") (name "/CH_RX") (class "Default")
      (node (ref "P1") (pin "2") (pinfunction "2_2") (pintype "passive"))
      (node (ref "U5") (pin "7") (pinfunction "RX_7") (pintype "passive"))
    )
    (net (code "8") (name "/CH_TX") (class "Default")
      (node (ref "P1") (pin "1") (pinfunction "1_1") (pintype "passive"))
      (node (ref "U5") (pin "6") (pinfunction "TX_6") (pintype "passive"))
    )
    (net (code "9") (name "/GSM_ANT") (class "Default")
      (node (ref "ANT1") (pin "2") (pinfunction "ant_2") (pintype "passive"))
      (node (ref "MC1") (pin "32") (pinfunction "GSM_ANT_32") (pintype "passive"))
    )
    (net (code "10") (name "/GSM_DTR") (class "Default")
      (node (ref "P2") (pin "6") (pinfunction "6_6") (pintype "passive"))
      (node (ref "R9") (pin "2") (pinfunction "2_2") (pintype "passive"))
    )
    (net (code "11") (name "/GSM_PWRKEY") (class "Default")
      (node (ref "P2") (pin "8") (pinfunction "8_8") (pintype "passive"))
      (node (ref "R19") (pin "1") (pinfunction "1_1") (pintype "passive"))
    )
    (net (code "12") (name "/GSM_RI") (class "Default")
      (node (ref "P2") (pin "7") (pinfunction "7_7") (pintype "passive"))
      (node (ref "R10") (pin "2") (pinfunction "2_2") (pintype "passive"))
    )
    (net (code "13") (name "/GSM_RX") (class "Default")
      (node (ref "P1") (pin "3") (pinfunction "3_3") (pintype "passive"))
      (node (ref "R2") (pin "2") (pinfunction "2_2") (pintype "passive"))
      (node (ref "R8") (pin "2") (pinfunction "2_2") (pintype "passive"))
    )
    (net (code "14") (name "/GSM_TX") (class "Default")
      (node (ref "P1") (pin "4") (pinfunction "4_4") (pintype "passive"))
      (node (ref "R1") (pin "2") (pinfunction "2_2") (pintype "passive"))
      (node (ref "R7") (pin "2") (pinfunction "2_2") (pintype "passive"))
    )
    (net (code "15") (name "/GSM_USB_N") (class "Default")
      (node (ref "J5") (pin "A7") (pinfunction "D-_A7") (pintype "passive"))
      (node (ref "J5") (pin "B7") (pinfunction "D-_B7") (pintype "passive"))
      (node (ref "R11") (pin "1") (pinfunction "1_1") (pintype "passive"))
      (node (ref "U4") (pin "6") (pinfunction "6_6") (pintype "passive"))
    )
    (net (code "16") (name "/GSM_USB_P") (class "Default")
      (node (ref "J5") (pin "A6") (pinfunction "D+_A6") (pintype "passive"))
      (node (ref "J5") (pin "B6") (pinfunction "D+_B6") (pintype "passive"))
      (node (ref "R12") (pin "1") (pinfunction "1_1") (pintype "passive"))
      (node (ref "U4") (pin "1") (pinfunction "1_1") (pintype "passive"))
    )
    (net (code "17") (name "/GSM_VRTC") (class "Default")
      (node (ref "MC1") (pin "28") (pinfunction "VRTC_28") (pintype "passive"))
      (node (ref "P2") (pin "9") (pinfunction "9_9") (pintype "passive"))
    )
    (net (code "18") (name "/MCU_RX") (class "Default")
      (node (ref "P1") (pin "6") (pinfunction "6_6") (pintype "passive"))
      (node (ref "P2") (pin "4") (pinfunction "4_4") (pintype "passive"))
    )
    (net (code "19") (name "/MCU_TX") (class "Default")
      (node (ref "P1") (pin "5") (pinfunction "5_5") (pintype "passive"))
      (node (ref "P2") (pin "5") (pinfunction "5_5") (pintype "passive"))
    )
    (net (code "20") (name "/MIC_N") (class "Default")
      (node (ref "C24") (pin "1") (pinfunction "1_1") (pintype "passive"))
      (node (ref "C25") (pin "1") (pinfunction "1_1") (pintype "passive"))
      (node (ref "C32") (pin "2") (pinfunction "2_2") (pintype "passive"))
      (node (ref "C33") (pin "2") (pinfunction "2_2") (pintype "passive"))
      (node (ref "D11") (pin "1") (pinfunction "K_1") (pintype "passive"))
      (node (ref "J3") (pin "1") (pinfunction "MIC_1") (pintype "passive"))
      (node (ref "MC1") (pin "10") (pinfunction "MICN_10") (pintype "passive"))
    )
    (net (code "21") (name "/MIC_P") (class "Default")
      (node (ref "C32") (pin "1") (pinfunction "1_1") (pintype "passive"))
      (node (ref "C33") (pin "1") (pinfunction "1_1") (pintype "passive"))
      (node (ref "C36") (pin "2") (pinfunction "2_2") (pintype "passive"))
      (node (ref "C37") (pin "2") (pinfunction "2_2") (pintype "passive"))
      (node (ref "D11") (pin "5") (pinfunction "K_5") (pintype "passive"))
      (node (ref "J3") (pin "4") (pinfunction "SP_Left_OUT_4") (pintype "passive"))
      (node (ref "MC1") (pin "9") (pinfunction "MICP_9") (pintype "passive"))
    )
    (net (code "22") (name "/NETLIGHT") (class "Default")
      (node (ref "MC1") (pin "41") (pinfunction "NETLIGHT_41") (pintype "passive"))
      (node (ref "R21") (pin "1") (pinfunction "1_1") (pintype "passive"))
    )
    (net (code "23") (name "/PWRKEY") (class "Default")
      (node (ref "D9") (pin "2") (pinfunction "2_2") (pintype "passive"))
      (node (ref "MC1") (pin "39") (pinfunction "PWRKEY_39") (pintype "passive"))
      (node (ref "Q1") (pin "3") (pinfunction "C_3") (pintype "passive"))
      (node (ref "SW1") (pin "2") (pinfunction "P3_2") (pintype "passive"))
    )
    (net (code "24") (name "/SIM_CLK") (class "Default")
      (node (ref "C29") (pin "2") (pinfunction "2_2") (pintype "passive"))
      (node (ref "MC1") (pin "16") (pinfunction "SIM_CLK_16") (pintype "passive"))
      (node (ref "R27") (pin "2") (pinfunction "2_2") (pintype "passive"))
    )
    (net (code "25") (name "/SIM_DATA") (class "Default")
      (node (ref "C27") (pin "2") (pinfunction "2_2") (pintype "passive"))
      (node (ref "MC1") (pin "15") (pinfunction "SIM_DATA_15") (pintype "passive"))
      (node (ref "R25") (pin "2") (pinfunction "2_2") (pintype "passive"))
    )
    (net (code "26") (name "/SIM_RST") (class "Default")
      (node (ref "C28") (pin "2") (pinfunction "2_2") (pintype "passive"))
      (node (ref "MC1") (pin "17") (pinfunction "SIM_RST_17") (pintype "passive"))
      (node (ref "R26") (pin "2") (pinfunction "2_2") (pintype "passive"))
    )
    (net (code "27") (name "/SIM_VCC") (class "Default")
      (node (ref "C26") (pin "2") (pinfunction "2_2") (pintype "passive"))
      (node (ref "D13") (pin "4") (pinfunction "K_4") (pintype "passive"))
      (node (ref "MC1") (pin "18") (pinfunction "SIM_VDD_18") (pintype "passive"))
      (node (ref "SIM1") (pin "1") (pinfunction "SIM_VCC_1") (pintype "passive"))
    )
    (net (code "28") (name "/SPK_N") (class "Default")
      (node (ref "C22") (pin "1") (pinfunction "1_1") (pintype "passive"))
      (node (ref "C23") (pin "1") (pinfunction "1_1") (pintype "passive"))
      (node (ref "C30") (pin "2") (pinfunction "2_2") (pintype "passive"))
      (node (ref "C31") (pin "2") (pinfunction "2_2") (pintype "passive"))
      (node (ref "D12") (pin "1") (pinfunction "K_1") (pintype "passive"))
      (node (ref "J2") (pin "1") (pinfunction "MIC_1") (pintype "passive"))
      (node (ref "MC1") (pin "12") (pinfunction "SPKN_12") (pintype "passive"))
    )
    (net (code "29") (name "/SPK_P") (class "Default")
      (node (ref "C30") (pin "1") (pinfunction "1_1") (pintype "passive"))
      (node (ref "C31") (pin "1") (pinfunction "1_1") (pintype "passive"))
      (node (ref "C34") (pin "2") (pinfunction "2_2") (pintype "passive"))
      (node (ref "C35") (pin "2") (pinfunction "2_2") (pintype "passive"))
      (node (ref "D12") (pin "5") (pinfunction "K_5") (pintype "passive"))
      (node (ref "J2") (pin "4") (pinfunction "SP_Left_OUT_4") (pintype "passive"))
      (node (ref "MC1") (pin "11") (pinfunction "SPKP_11") (pintype "passive"))
    )
    (net (code "30") (name "/STATUS") (class "Default")
      (node (ref "MC1") (pin "42") (pinfunction "STATUS_42") (pintype "passive"))
      (node (ref "R20") (pin "1") (pinfunction "1_1") (pintype "passive"))
    )
    (net (code "31") (name "GND") (class "Default")
      (node (ref "ANT1") (pin "1") (pinfunction "gnd_1") (pintype "passive"))
      (node (ref "C10") (pin "1") (pinfunction "1_1") (pintype "passive"))
      (node (ref "C11") (pin "1") (pinfunction "1_1") (pintype "passive"))
      (node (ref "C12") (pin "2") (pinfunction "-_2") (pintype "passive"))
      (node (ref "C13") (pin "2") (pinfunction "-_2") (pintype "passive"))
      (node (ref "C14") (pin "2") (pinfunction "2_2") (pintype "passive"))
      (node (ref "C15") (pin "2") (pinfunction "2_2") (pintype "passive"))
      (node (ref "C16") (pin "1") (pinfunction "1_1") (pintype "passive"))
      (node (ref "C17") (pin "1") (pinfunction "1_1") (pintype "passive"))
      (node (ref "C18") (pin "1") (pinfunction "1_1") (pintype "passive"))
      (node (ref "C19") (pin "2") (pinfunction "2_2") (pintype "passive"))
      (node (ref "C2") (pin "2") (pinfunction "-_2") (pintype "passive"))
      (node (ref "C20") (pin "1") (pinfunction "1_1") (pintype "passive"))
      (node (ref "C21") (pin "2") (pinfunction "2_2") (pintype "passive"))
      (node (ref "C22") (pin "2") (pinfunction "2_2") (pintype "passive"))
      (node (ref "C23") (pin "2") (pinfunction "2_2") (pintype "passive"))
      (node (ref "C24") (pin "2") (pinfunction "2_2") (pintype "passive"))
      (node (ref "C25") (pin "2") (pinfunction "2_2") (pintype "passive"))
      (node (ref "C26") (pin "1") (pinfunction "1_1") (pintype "passive"))
      (node (ref "C27") (pin "1") (pinfunction "1_1") (pintype "passive"))
      (node (ref "C28") (pin "1") (pinfunction "1_1") (pintype "passive"))
      (node (ref "C29") (pin "1") (pinfunction "1_1") (pintype "passive"))
      (node (ref "C3") (pin "1") (pinfunction "1_1") (pintype "passive"))
      (node (ref "C34") (pin "1") (pinfunction "1_1") (pintype "passive"))
      (node (ref "C35") (pin "1") (pinfunction "1_1") (pintype "passive"))
      (node (ref "C36") (pin "1") (pinfunction "1_1") (pintype "passive"))
      (node (ref "C37") (pin "1") (pinfunction "1_1") (pintype "passive"))
      (node (ref "C38") (pin "1") (pinfunction "1_1") (pintype "passive"))
      (node (ref "C39") (pin "1") (pinfunction "1_1") (pintype "passive"))
      (node (ref "C4") (pin "1") (pinfunction "1_1") (pintype "passive"))
      (node (ref "C40") (pin "1") (pinfunction "1_1") (pintype "passive"))
      (node (ref "C41") (pin "1") (pinfunction "1_1") (pintype "passive"))
      (node (ref "C42") (pin "1") (pinfunction "1_1") (pintype "passive"))
      (node (ref "C43") (pin "1") (pinfunction "1_1") (pintype "passive"))
      (node (ref "C5") (pin "2") (pinfunction "2_2") (pintype "passive"))
      (node (ref "C6") (pin "2") (pinfunction "2_2") (pintype "passive"))
      (node (ref "C7") (pin "1") (pinfunction "1_1") (pintype "passive"))
      (node (ref "C9") (pin "1") (pinfunction "1_1") (pintype "passive"))
      (node (ref "D10") (pin "1") (pinfunction "1_1") (pintype "passive"))
      (node (ref "D11") (pin "2") (pinfunction "K_2") (pintype "passive"))
      (node (ref "D12") (pin "2") (pinfunction "K_2") (pintype "passive"))
      (node (ref "D13") (pin "2") (pinfunction "K_2") (pintype "passive"))
      (node (ref "D3") (pin "1") (pinfunction "1_1") (pintype "passive"))
      (node (ref "D4") (pin "A") (pinfunction "A_A") (pintype "passive"))
      (node (ref "D6") (pin "1") (pinfunction "1_1") (pintype "passive"))
      (node (ref "D9") (pin "1") (pinfunction "1_1") (pintype "passive"))
      (node (ref "J1") (pin "1") (pinfunction "1_1") (pintype "passive"))
      (node (ref "J4") (pin "2") (pinfunction "G1_2") (pintype "passive"))
      (node (ref "J4") (pin "3") (pinfunction "G2_3") (pintype "passive"))
      (node (ref "J5") (pin "A1B12") (pinfunction "GND_A1B12") (pintype "passive"))
      (node (ref "J5") (pin "B1A12") (pinfunction "GND_B1A12") (pintype "passive"))
      (node (ref "J5") (pin "SH1") (pinfunction "SH1_SH1") (pintype "passive"))
      (node (ref "J5") (pin "SH2") (pinfunction "SH2_SH2") (pintype "passive"))
      (node (ref "J5") (pin "SH3") (pinfunction "SH3_SH3") (pintype "passive"))
      (node (ref "J5") (pin "SH4") (pinfunction "SH4_SH4") (pintype "passive"))
      (node (ref "J6") (pin "A1B12") (pinfunction "GND_A1B12") (pintype "passive"))
      (node (ref "J6") (pin "B1A12") (pinfunction "GND_B1A12") (pintype "passive"))
      (node (ref "J6") (pin "SH1") (pinfunction "SH1_SH1") (pintype "passive"))
      (node (ref "J6") (pin "SH2") (pinfunction "SH2_SH2") (pintype "passive"))
      (node (ref "J6") (pin "SH3") (pinfunction "SH3_SH3") (pintype "passive"))
      (node (ref "J6") (pin "SH4") (pinfunction "SH4_SH4") (pintype "passive"))
      (node (ref "MC1") (pin "13") (pinfunction "GND_13") (pintype "passive"))
      (node (ref "MC1") (pin "19") (pinfunction "GND_19") (pintype "passive"))
      (node (ref "MC1") (pin "21") (pinfunction "GND_21") (pintype "passive"))
      (node (ref "MC1") (pin "27") (pinfunction "GND_27") (pintype "passive"))
      (node (ref "MC1") (pin "30") (pinfunction "GND_30") (pintype "passive"))
      (node (ref "MC1") (pin "31") (pinfunction "GND_31") (pintype "passive"))
      (node (ref "MC1") (pin "33") (pinfunction "GND_33") (pintype "passive"))
      (node (ref "MC1") (pin "36") (pinfunction "GND_36") (pintype "passive"))
      (node (ref "MC1") (pin "37") (pinfunction "GND_37") (pintype "passive"))
      (node (ref "MC1") (pin "8") (pinfunction "GND_8") (pintype "passive"))
      (node (ref "P2") (pin "1") (pinfunction "1_1") (pintype "passive"))
      (node (ref "P2") (pin "10") (pinfunction "10_10") (pintype "passive"))
      (node (ref "Q1") (pin "2") (pinfunction "E_2") (pintype "passive"))
      (node (ref "Q2") (pin "2") (pinfunction "E_2") (pintype "passive"))
      (node (ref "Q3") (pin "2") (pinfunction "E_2") (pintype "passive"))
      (node (ref "R13") (pin "1") (pinfunction "1_1") (pintype "passive"))
      (node (ref "R14") (pin "1") (pinfunction "1_1") (pintype "passive"))
      (node (ref "R16") (pin "1") (pinfunction "1_1") (pintype "passive"))
      (node (ref "R22") (pin "1") (pinfunction "1_1") (pintype "passive"))
      (node (ref "R23") (pin "1") (pinfunction "1_1") (pintype "passive"))
      (node (ref "R24") (pin "1") (pinfunction "1_1") (pintype "passive"))
      (node (ref "R28") (pin "1") (pinfunction "1_1") (pintype "passive"))
      (node (ref "R29") (pin "1") (pinfunction "1_1") (pintype "passive"))
      (node (ref "R3") (pin "1") (pinfunction "1_1") (pintype "passive"))
      (node (ref "R30") (pin "2") (pinfunction "2_2") (pintype "passive"))
      (node (ref "R31") (pin "2") (pinfunction "2_2") (pintype "passive"))
      (node (ref "R32") (pin "1") (pinfunction "1_1") (pintype "passive"))
      (node (ref "R33") (pin "1") (pinfunction "1_1") (pintype "passive"))
      (node (ref "R4") (pin "1") (pinfunction "1_1") (pintype "passive"))
      (node (ref "SIM1") (pin "5") (pinfunction "GND_5") (pintype "passive"))
      (node (ref "SW1") (pin "1") (pinfunction "P1_1") (pintype "passive"))
      (node (ref "U1") (pin "1") (pinfunction "GND_1") (pintype "power_in"))
      (node (ref "U2") (pin "3") (pinfunction "GND_3") (pintype "bidirectional"))
      (node (ref "U2") (pin "6") (pinfunction "TAB_6") (pintype "bidirectional"))
      (node (ref "U3") (pin "2") (pinfunction "GND_2") (pintype "passive"))
      (node (ref "U3") (pin "4") (pinfunction "NC_4") (pintype "passive"))
      (node (ref "U4") (pin "2") (pinfunction "2_2") (pintype "passive"))
      (node (ref "U5") (pin "3") (pinfunction "GND_3") (pintype "passive"))
      (node (ref "U6") (pin "2") (pinfunction "2_2") (pintype "passive"))
    )
    (net (code "32") (name "Net-(C2-+)") (class "Default")
      (node (ref "C2") (pin "1") (pinfunction "+_1") (pintype "passive"))
      (node (ref "C3") (pin "2") (pinfunction "2_2") (pintype "passive"))
      (node (ref "C4") (pin "2") (pinfunction "2_2") (pintype "passive"))
      (node (ref "D3") (pin "2") (pinfunction "2_2") (pintype "passive"))
      (node (ref "D4") (pin "C") (pinfunction "C_C") (pintype "passive"))
      (node (ref "F1") (pin "2") (pinfunction "2_2") (pintype "passive"))
      (node (ref "TPINPUT1") (pin "1") (pinfunction "1_1") (pintype "passive"))
      (node (ref "U1") (pin "3") (pinfunction "VIN_3") (pintype "power_in"))
      (node (ref "U1") (pin "5") (pinfunction "EN_5") (pintype "input"))
    )
    (net (code "33") (name "Net-(C8-Pad2)") (class "Default")
      (node (ref "C8") (pin "2") (pinfunction "2_2") (pintype "passive"))
      (node (ref "R5") (pin "2") (pinfunction "2_2") (pintype "passive"))
      (node (ref "R6") (pin "1") (pinfunction "1_1") (pintype "passive"))
    )
    (net (code "34") (name "Net-(C40-Pad2)") (class "Default")
      (node (ref "C40") (pin "2") (pinfunction "2_2") (pintype "passive"))
      (node (ref "F2") (pin "1") (pinfunction "1_1") (pintype "passive"))
      (node (ref "FB1") (pin "2") (pinfunction "2_2") (pintype "passive"))
    )
    (net (code "35") (name "Net-(D1-CATHODE)") (class "Default")
      (node (ref "D1") (pin "2") (pinfunction "CATHODE_2") (pintype "passive"))
      (node (ref "R1") (pin "1") (pinfunction "1_1") (pintype "passive"))
    )
    (net (code "36") (name "Net-(D2-CATHODE)") (class "Default")
      (node (ref "D2") (pin "2") (pinfunction "CATHODE_2") (pintype "passive"))
      (node (ref "R2") (pin "1") (pinfunction "1_1") (pintype "passive"))
    )
    (net (code "37") (name "Net-(D5-CATHODE)") (class "Default")
      (node (ref "D5") (pin "2") (pinfunction "CATHODE_2") (pintype "passive"))
      (node (ref "R13") (pin "2") (pinfunction "2_2") (pintype "passive"))
    )
    (net (code "38") (name "Net-(D7-CATHODE)") (class "Default")
      (node (ref "D7") (pin "2") (pinfunction "CATHODE_2") (pintype "passive"))
      (node (ref "R18") (pin "2") (pinfunction "2_2") (pintype "passive"))
    )
    (net (code "39") (name "Net-(D8-CATHODE)") (class "Default")
      (node (ref "D8") (pin "2") (pinfunction "CATHODE_2") (pintype "passive"))
      (node (ref "R17") (pin "2") (pinfunction "2_2") (pintype "passive"))
    )
    (net (code "40") (name "Net-(D14-CATHODE)") (class "Default")
      (node (ref "D14") (pin "2") (pinfunction "CATHODE_2") (pintype "passive"))
      (node (ref "R32") (pin "2") (pinfunction "2_2") (pintype "passive"))
    )
    (net (code "41") (name "Net-(D15-CATHODE)") (class "Default")
      (node (ref "D15") (pin "2") (pinfunction "CATHODE_2") (pintype "passive"))
      (node (ref "R33") (pin "2") (pinfunction "2_2") (pintype "passive"))
    )
    (net (code "42") (name "Net-(F2-Pad2)") (class "Default")
      (node (ref "F2") (pin "2") (pinfunction "2_2") (pintype "passive"))
      (node (ref "J5") (pin "A4B9") (pinfunction "VBUS_A4B9") (pintype "passive"))
      (node (ref "J5") (pin "B4A9") (pinfunction "VBUS_B4A9") (pintype "passive"))
    )
    (net (code "43") (name "Net-(F3-Pad2)") (class "Default")
      (node (ref "F3") (pin "2") (pinfunction "2_2") (pintype "passive"))
      (node (ref "J6") (pin "A4B9") (pinfunction "VBUS_A4B9") (pintype "passive"))
      (node (ref "J6") (pin "B4A9") (pinfunction "VBUS_B4A9") (pintype "passive"))
    )
    (net (code "44") (name "Net-(J5-CC1)") (class "Default")
      (node (ref "J5") (pin "A5") (pinfunction "CC1_A5") (pintype "passive"))
      (node (ref "R28") (pin "2") (pinfunction "2_2") (pintype "passive"))
    )
    (net (code "45") (name "Net-(J5-CC2)") (class "Default")
      (node (ref "J5") (pin "B5") (pinfunction "CC2_B5") (pintype "passive"))
      (node (ref "R30") (pin "1") (pinfunction "1_1") (pintype "passive"))
    )
    (net (code "46") (name "Net-(J6-CC1)") (class "Default")
      (node (ref "J6") (pin "A5") (pinfunction "CC1_A5") (pintype "passive"))
      (node (ref "R29") (pin "2") (pinfunction "2_2") (pintype "passive"))
    )
    (net (code "47") (name "Net-(J6-CC2)") (class "Default")
      (node (ref "J6") (pin "B5") (pinfunction "CC2_B5") (pintype "passive"))
      (node (ref "R31") (pin "1") (pinfunction "1_1") (pintype "passive"))
    )
    (net (code "48") (name "Net-(MC1-UART1_DTR)") (class "Default")
      (node (ref "MC1") (pin "6") (pinfunction "UART1_DTR_6") (pintype "passive"))
      (node (ref "R14") (pin "2") (pinfunction "2_2") (pintype "passive"))
      (node (ref "R9") (pin "1") (pinfunction "1_1") (pintype "passive"))
    )
    (net (code "49") (name "Net-(MC1-UART1_RI)") (class "Default")
      (node (ref "MC1") (pin "7") (pinfunction "UART1_RI_7") (pintype "passive"))
      (node (ref "R10") (pin "1") (pinfunction "1_1") (pintype "passive"))
    )
    (net (code "50") (name "Net-(MC1-UART1_RXD)") (class "Default")
      (node (ref "MC1") (pin "2") (pinfunction "UART1_RXD_2") (pintype "passive"))
      (node (ref "R3") (pin "2") (pinfunction "2_2") (pintype "passive"))
      (node (ref "R8") (pin "1") (pinfunction "1_1") (pintype "passive"))
    )
    (net (code "51") (name "Net-(MC1-UART1_TXD)") (class "Default")
      (node (ref "MC1") (pin "1") (pinfunction "UART1_TXD_1") (pintype "passive"))
      (node (ref "R7") (pin "1") (pinfunction "1_1") (pintype "passive"))
    )
    (net (code "52") (name "Net-(MC1-USB_DN)") (class "Default")
      (node (ref "MC1") (pin "26") (pinfunction "USB_DN_26") (pintype "passive"))
      (node (ref "R11") (pin "2") (pinfunction "2_2") (pintype "passive"))
    )
    (net (code "53") (name "Net-(MC1-USB_DP)") (class "Default")
      (node (ref "MC1") (pin "25") (pinfunction "USB_DP_25") (pintype "passive"))
      (node (ref "R12") (pin "2") (pinfunction "2_2") (pintype "passive"))
    )
    (net (code "54") (name "Net-(Q1-B)") (class "Default")
      (node (ref "Q1") (pin "1") (pinfunction "B_1") (pintype "passive"))
      (node (ref "R19") (pin "2") (pinfunction "2_2") (pintype "passive"))
      (node (ref "R22") (pin "2") (pinfunction "2_2") (pintype "passive"))
    )
    (net (code "55") (name "Net-(Q2-B)") (class "Default")
      (node (ref "Q2") (pin "1") (pinfunction "B_1") (pintype "passive"))
      (node (ref "R20") (pin "2") (pinfunction "2_2") (pintype "passive"))
      (node (ref "R23") (pin "2") (pinfunction "2_2") (pintype "passive"))
    )
    (net (code "56") (name "Net-(Q2-C)") (class "Default")
      (node (ref "Q2") (pin "3") (pinfunction "C_3") (pintype "passive"))
      (node (ref "R18") (pin "1") (pinfunction "1_1") (pintype "passive"))
    )
    (net (code "57") (name "Net-(Q3-B)") (class "Default")
      (node (ref "Q3") (pin "1") (pinfunction "B_1") (pintype "passive"))
      (node (ref "R21") (pin "2") (pinfunction "2_2") (pintype "passive"))
      (node (ref "R24") (pin "2") (pinfunction "2_2") (pintype "passive"))
    )
    (net (code "58") (name "Net-(Q3-C)") (class "Default")
      (node (ref "Q3") (pin "3") (pinfunction "C_3") (pintype "passive"))
      (node (ref "R17") (pin "1") (pinfunction "1_1") (pintype "passive"))
    )
    (net (code "59") (name "Net-(SIM1-SIM_CLK)") (class "Default")
      (node (ref "D13") (pin "3") (pinfunction "K_3") (pintype "passive"))
      (node (ref "R27") (pin "1") (pinfunction "1_1") (pintype "passive"))
      (node (ref "SIM1") (pin "3") (pinfunction "SIM_CLK_3") (pintype "passive"))
    )
    (net (code "60") (name "Net-(SIM1-SIM_DATA)") (class "Default")
      (node (ref "D13") (pin "1") (pinfunction "K_1") (pintype "passive"))
      (node (ref "R25") (pin "1") (pinfunction "1_1") (pintype "passive"))
      (node (ref "SIM1") (pin "7") (pinfunction "SIM_DATA_7") (pintype "passive"))
    )
    (net (code "61") (name "Net-(SIM1-SIM_RST)") (class "Default")
      (node (ref "D13") (pin "5") (pinfunction "K_5") (pintype "passive"))
      (node (ref "R26") (pin "1") (pinfunction "1_1") (pintype "passive"))
      (node (ref "SIM1") (pin "2") (pinfunction "SIM_RST_2") (pintype "passive"))
    )
    (net (code "62") (name "Net-(U1-BOOT)") (class "Default")
      (node (ref "C1") (pin "1") (pinfunction "1_1") (pintype "passive"))
      (node (ref "U1") (pin "6") (pinfunction "BOOT_6") (pintype "output"))
    )
    (net (code "63") (name "Net-(U1-FB)") (class "Default")
      (node (ref "C8") (pin "1") (pinfunction "1_1") (pintype "passive"))
      (node (ref "R4") (pin "2") (pinfunction "2_2") (pintype "passive"))
      (node (ref "R5") (pin "1") (pinfunction "1_1") (pintype "passive"))
      (node (ref "U1") (pin "4") (pinfunction "FB_4") (pintype "input"))
    )
    (net (code "64") (name "Net-(U1-SW)") (class "Default")
      (node (ref "C1") (pin "2") (pinfunction "2_2") (pintype "passive"))
      (node (ref "L1") (pin "1") (pinfunction "1_1") (pintype "passive"))
      (node (ref "U1") (pin "2") (pinfunction "SW_2") (pintype "output"))
    )
    (net (code "65") (name "Net-(U2-ADJ)") (class "Default")
      (node (ref "R15") (pin "1") (pinfunction "1_1") (pintype "passive"))
      (node (ref "R16") (pin "2") (pinfunction "2_2") (pintype "passive"))
      (node (ref "U2") (pin "5") (pinfunction "ADJ_5") (pintype "bidirectional"))
    )
    (net (code "66") (name "VBAT") (class "Default")
      (node (ref "C10") (pin "2") (pinfunction "2_2") (pintype "passive"))
      (node (ref "C11") (pin "2") (pinfunction "2_2") (pintype "passive"))
      (node (ref "C12") (pin "1") (pinfunction "+_1") (pintype "passive"))
      (node (ref "C13") (pin "1") (pinfunction "+_1") (pintype "passive"))
      (node (ref "C14") (pin "1") (pinfunction "1_1") (pintype "passive"))
      (node (ref "C15") (pin "1") (pinfunction "1_1") (pintype "passive"))
      (node (ref "C16") (pin "2") (pinfunction "2_2") (pintype "passive"))
      (node (ref "C17") (pin "2") (pinfunction "2_2") (pintype "passive"))
      (node (ref "C18") (pin "2") (pinfunction "2_2") (pintype "passive"))
      (node (ref "D5") (pin "1") (pinfunction "ANODE_1") (pintype "passive"))
      (node (ref "D6") (pin "2") (pinfunction "2_2") (pintype "passive"))
      (node (ref "D7") (pin "1") (pinfunction "ANODE_1") (pintype "passive"))
      (node (ref "D8") (pin "1") (pinfunction "ANODE_1") (pintype "passive"))
      (node (ref "MC1") (pin "34") (pinfunction "VBAT_34") (pintype "passive"))
      (node (ref "MC1") (pin "35") (pinfunction "VBAT_35") (pintype "passive"))
      (node (ref "R15") (pin "2") (pinfunction "2_2") (pintype "passive"))
      (node (ref "TP2") (pin "1") (pinfunction "1_1") (pintype "passive"))
      (node (ref "U2") (pin "4") (pinfunction "OUT_4") (pintype "bidirectional"))
    )
    (net (code "67") (name "VBUS1") (class "Default")
      (node (ref "C38") (pin "2") (pinfunction "2_2") (pintype "passive"))
      (node (ref "C39") (pin "2") (pinfunction "2_2") (pintype "passive"))
      (node (ref "D14") (pin "1") (pinfunction "ANODE_1") (pintype "passive"))
      (node (ref "FB1") (pin "1") (pinfunction "1_1") (pintype "passive"))
      (node (ref "MC1") (pin "24") (pinfunction "USB_VBUS_24") (pintype "passive"))
      (node (ref "U4") (pin "5") (pinfunction "5_5") (pintype "passive"))
    )
    (net (code "68") (name "VBUS2") (class "Default")
      (node (ref "C41") (pin "2") (pinfunction "2_2") (pintype "passive"))
      (node (ref "C42") (pin "2") (pinfunction "2_2") (pintype "passive"))
      (node (ref "D15") (pin "1") (pinfunction "ANODE_1") (pintype "passive"))
      (node (ref "F3") (pin "1") (pinfunction "1_1") (pintype "passive"))
      (node (ref "U6") (pin "5") (pinfunction "5_5") (pintype "passive"))
    )
    (net (code "69") (name "unconnected-(D11-K-Pad3)") (class "Default")
      (node (ref "D11") (pin "3") (pinfunction "K_3") (pintype "passive+no_connect"))
    )
    (net (code "70") (name "unconnected-(D11-K-Pad4)") (class "Default")
      (node (ref "D11") (pin "4") (pinfunction "K_4") (pintype "passive+no_connect"))
    )
    (net (code "71") (name "unconnected-(D12-K-Pad3)") (class "Default")
      (node (ref "D12") (pin "3") (pinfunction "K_3") (pintype "passive+no_connect"))
    )
    (net (code "72") (name "unconnected-(D12-K-Pad4)") (class "Default")
      (node (ref "D12") (pin "4") (pinfunction "K_4") (pintype "passive+no_connect"))
    )
    (net (code "73") (name "unconnected-(J2-GND-Pad2)") (class "Default")
      (node (ref "J2") (pin "2") (pinfunction "GND_2") (pintype "passive+no_connect"))
    )
    (net (code "74") (name "unconnected-(J2-SP_Left_IN-Pad5)") (class "Default")
      (node (ref "J2") (pin "5") (pinfunction "SP_Left_IN_5") (pintype "passive+no_connect"))
    )
    (net (code "75") (name "unconnected-(J2-SP_Right_IN-Pad6)") (class "Default")
      (node (ref "J2") (pin "6") (pinfunction "SP_Right_IN_6") (pintype "passive+no_connect"))
    )
    (net (code "76") (name "unconnected-(J2-SP_Right_OUT-Pad3)") (class "Default")
      (node (ref "J2") (pin "3") (pinfunction "SP_Right_OUT_3") (pintype "passive+no_connect"))
    )
    (net (code "77") (name "unconnected-(J3-GND-Pad2)") (class "Default")
      (node (ref "J3") (pin "2") (pinfunction "GND_2") (pintype "passive+no_connect"))
    )
    (net (code "78") (name "unconnected-(J3-SP_Left_IN-Pad5)") (class "Default")
      (node (ref "J3") (pin "5") (pinfunction "SP_Left_IN_5") (pintype "passive+no_connect"))
    )
    (net (code "79") (name "unconnected-(J3-SP_Right_IN-Pad6)") (class "Default")
      (node (ref "J3") (pin "6") (pinfunction "SP_Right_IN_6") (pintype "passive+no_connect"))
    )
    (net (code "80") (name "unconnected-(J3-SP_Right_OUT-Pad3)") (class "Default")
      (node (ref "J3") (pin "3") (pinfunction "SP_Right_OUT_3") (pintype "passive+no_connect"))
    )
    (net (code "81") (name "unconnected-(J5-SBU1-PadA8)") (class "Default")
      (node (ref "J5") (pin "A8") (pinfunction "SBU1_A8") (pintype "passive+no_connect"))
    )
    (net (code "82") (name "unconnected-(J5-SBU2-PadB8)") (class "Default")
      (node (ref "J5") (pin "B8") (pinfunction "SBU2_B8") (pintype "passive+no_connect"))
    )
    (net (code "83") (name "unconnected-(J6-SBU1-PadA8)") (class "Default")
      (node (ref "J6") (pin "A8") (pinfunction "SBU1_A8") (pintype "passive+no_connect"))
    )
    (net (code "84") (name "unconnected-(J6-SBU2-PadB8)") (class "Default")
      (node (ref "J6") (pin "B8") (pinfunction "SBU2_B8") (pintype "passive+no_connect"))
    )
    (net (code "85") (name "unconnected-(MC1-ADC-Pad38)") (class "Default")
      (node (ref "MC1") (pin "38") (pinfunction "ADC_38") (pintype "passive+no_connect"))
    )
    (net (code "86") (name "unconnected-(MC1-RF_SYNC-Pad29)") (class "Default")
      (node (ref "MC1") (pin "29") (pinfunction "RF_SYNC_29") (pintype "passive+no_connect"))
    )
    (net (code "87") (name "unconnected-(MC1-SIM_DET-Pad14)") (class "Default")
      (node (ref "MC1") (pin "14") (pinfunction "SIM_DET_14") (pintype "passive+no_connect"))
    )
    (net (code "88") (name "unconnected-(MC1-UART1_CTS-Pad4)") (class "Default")
      (node (ref "MC1") (pin "4") (pinfunction "UART1_CTS_4") (pintype "passive+no_connect"))
    )
    (net (code "89") (name "unconnected-(MC1-UART1_DCD-Pad5)") (class "Default")
      (node (ref "MC1") (pin "5") (pinfunction "UART1_DCD_5") (pintype "passive+no_connect"))
    )
    (net (code "90") (name "unconnected-(MC1-UART1_RTS-Pad3)") (class "Default")
      (node (ref "MC1") (pin "3") (pinfunction "UART1_RTS_3") (pintype "passive+no_connect"))
    )
    (net (code "91") (name "unconnected-(MC1-UART2_RXD-Pad23)") (class "Default")
      (node (ref "MC1") (pin "23") (pinfunction "UART2_RXD_23") (pintype "passive+no_connect"))
    )
    (net (code "92") (name "unconnected-(MC1-UART2_TXD-Pad22)") (class "Default")
      (node (ref "MC1") (pin "22") (pinfunction "UART2_TXD_22") (pintype "passive+no_connect"))
    )
    (net (code "93") (name "unconnected-(MC1-VDD_EXT-Pad40)") (class "Default")
      (node (ref "MC1") (pin "40") (pinfunction "VDD_EXT_40") (pintype "passive+no_connect"))
    )
    (net (code "94") (name "unconnected-(SIM1-SIM_VPP-Pad6)") (class "Default")
      (node (ref "SIM1") (pin "6") (pinfunction "SIM_VPP_6") (pintype "passive+no_connect"))
    )
    (net (code "95") (name "unconnected-(U4-Pad3)") (class "Default")
      (node (ref "U4") (pin "3") (pinfunction "3_3") (pintype "passive+no_connect"))
    )
    (net (code "96") (name "unconnected-(U4-Pad4)") (class "Default")
      (node (ref "U4") (pin "4") (pinfunction "4_4") (pintype "passive+no_connect"))
    )
    (net (code "97") (name "unconnected-(U5-RTS-Pad4)") (class "Default")
      (node (ref "U5") (pin "4") (pinfunction "RTS_4") (pintype "passive+no_connect"))
    )
    (net (code "98") (name "unconnected-(U6-Pad1)") (class "Default")
      (node (ref "U6") (pin "1") (pinfunction "1_1") (pintype "passive+no_connect"))
    )
    (net (code "99") (name "unconnected-(U6-Pad3)") (class "Default")
      (node (ref "U6") (pin "3") (pinfunction "3_3") (pintype "passive+no_connect"))
    )
  )
)
